# Beacon.net
KiCad netlist of a schematic drawn in Altium Designer
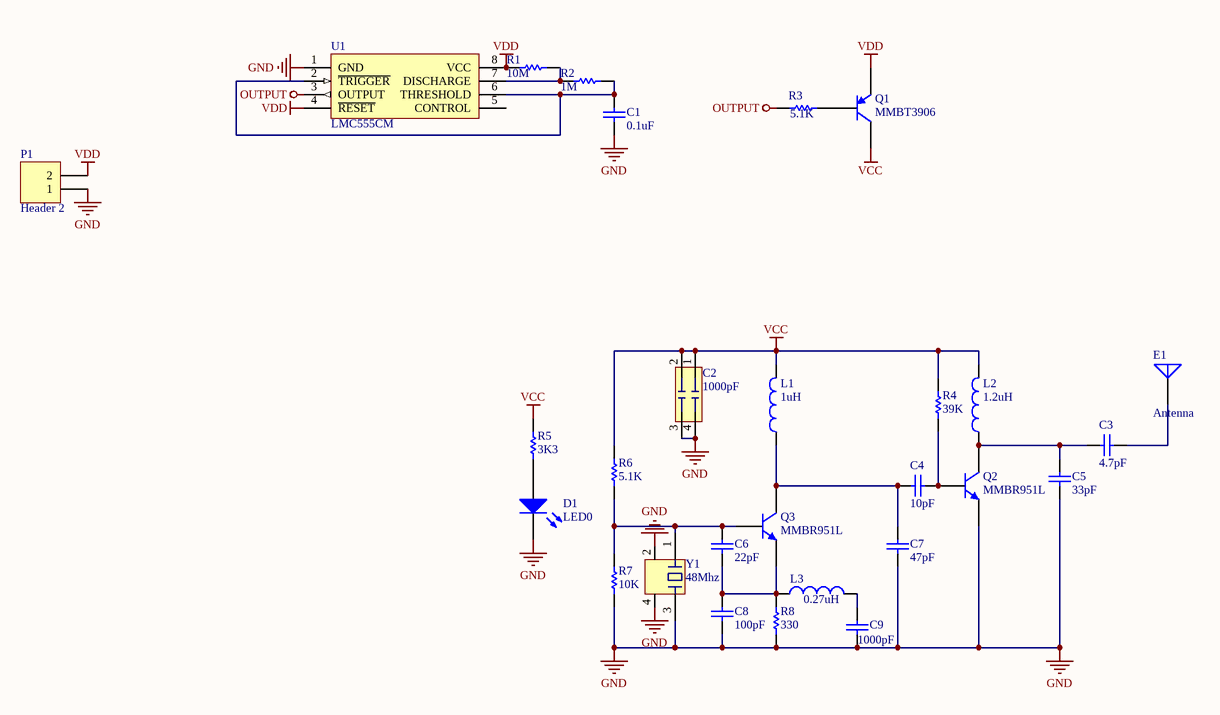
[diagram p0: Beacon.SchDoc]

(export (version "E")
  (design (tool "Eeschema 10.0.6"))
  (components
    (comp (ref "C1")
      (value "0.1uF")
      (footprint "0603")
      (description "Capacitor")
      (fields (field (name "PUBLISHER") "Altium Limited"))
      (libsource (lib "Miscellaneous Devices") (part "Cap"))
    )
    (comp (ref "C2") (value "1000pF") (footprint "CKCL22") (libsource (lib "Mert") (part "CAP ARRAY 2")))
    (comp (ref "C3")
      (value "4.7pF")
      (footprint "0402")
      (description "Capacitor")
      (fields (field (name "PUBLISHER") "Altium Limited"))
      (libsource (lib "Miscellaneous Devices") (part "Cap"))
    )
    (comp (ref "C4")
      (value "10pF")
      (footprint "0402")
      (description "Capacitor")
      (fields (field (name "PUBLISHER") "Altium Limited"))
      (libsource (lib "Miscellaneous Devices") (part "Cap"))
    )
    (comp (ref "C5")
      (value "33pF")
      (footprint "0402")
      (description "Capacitor")
      (fields (field (name "PUBLISHER") "Altium Limited"))
      (libsource (lib "Miscellaneous Devices") (part "Cap"))
    )
    (comp (ref "C6")
      (value "22pF")
      (footprint "0402")
      (description "Capacitor")
      (fields (field (name "PUBLISHER") "Altium Limited"))
      (libsource (lib "Miscellaneous Devices") (part "Cap"))
    )
    (comp (ref "C7")
      (value "47pF")
      (footprint "0402")
      (description "Capacitor")
      (fields (field (name "PUBLISHER") "Altium Limited"))
      (libsource (lib "Miscellaneous Devices") (part "Cap"))
    )
    (comp (ref "C8")
      (value "100pF")
      (footprint "0402")
      (description "Capacitor")
      (fields (field (name "PUBLISHER") "Altium Limited"))
      (libsource (lib "Miscellaneous Devices") (part "Cap"))
    )
    (comp (ref "C9")
      (value "1000pF")
      (footprint "0402")
      (description "Capacitor")
      (fields (field (name "PUBLISHER") "Altium Limited"))
      (libsource (lib "Miscellaneous Devices") (part "Cap"))
    )
    (comp (ref "D1")
      (value "LED0")
      (footprint "0402")
      (description "Typical INFRARED GaAs LED")
      (fields (field (name "PUBLISHER") "Altium Limited"))
      (libsource (lib "Miscellaneous Devices") (part "LED0"))
    )
    (comp (ref "E1")
      (value "Antenna")
      (footprint "PIN1")
      (description "Generic Antenna")
      (fields (field (name "PUBLISHER") "Altium Limited"))
      (libsource (lib "Miscellaneous Devices") (part "Antenna"))
    )
    (comp (ref "L1")
      (value "1uH")
      (footprint "1008")
      (description "Inductor")
      (fields (field (name "PUBLISHER") "Altium Limited"))
      (libsource (lib "Miscellaneous Devices") (part "Inductor"))
    )
    (comp (ref "L2")
      (value "1.2uH")
      (footprint "1008")
      (description "Inductor")
      (fields (field (name "PUBLISHER") "Altium Limited"))
      (libsource (lib "Miscellaneous Devices") (part "Inductor"))
    )
    (comp (ref "L3")
      (value "0.27uH")
      (footprint "0402")
      (description "Inductor")
      (fields (field (name "PUBLISHER") "Altium Limited"))
      (libsource (lib "Miscellaneous Devices") (part "Inductor"))
    )
    (comp (ref "P1")
      (value "Header 2")
      (footprint "HDR1X2")
      (description "Header, 2-Pin")
      (fields (field (name "PUBLISHER") "Altium Limited"))
      (libsource (lib "Miscellaneous Connectors") (part "Header 2"))
    )
    (comp (ref "Q1")
      (value "MMBT3906")
      (footprint "sot-923f")
      (description "PNP Switching Transistor")
      (fields (field (name "PUBLISHER") "Altium Limited"))
      (libsource (lib "Philips Discrete BJT - Low Power") (part "MMBT3906"))
    )
    (comp (ref "Q2")
      (value "MMBR951L")
      (footprint "sot-23")
      (description "NPN Bipolar Transistor")
      (fields (field (name "PUBLISHER") "Altium Limited"))
      (libsource (lib "Miscellaneous Devices") (part "NPN"))
    )
    (comp (ref "Q3")
      (value "MMBR951L")
      (footprint "sot-23")
      (description "NPN Bipolar Transistor")
      (fields (field (name "PUBLISHER") "Altium Limited"))
      (libsource (lib "Miscellaneous Devices") (part "NPN"))
    )
    (comp (ref "R1")
      (value "10M")
      (footprint "0402")
      (description "Resistor")
      (fields (field (name "PUBLISHER") "Altium Limited"))
      (libsource (lib "Miscellaneous Devices") (part "Res1"))
    )
    (comp (ref "R2")
      (value "1M")
      (footprint "0603")
      (description "Resistor")
      (fields (field (name "PUBLISHER") "Altium Limited"))
      (libsource (lib "Miscellaneous Devices") (part "Res1"))
    )
    (comp (ref "R3")
      (value "5.1K")
      (footprint "0402")
      (description "Resistor")
      (fields (field (name "PUBLISHER") "Altium Limited"))
      (libsource (lib "Miscellaneous Devices") (part "Res1"))
    )
    (comp (ref "R4")
      (value "39K")
      (footprint "0402")
      (description "Resistor")
      (fields (field (name "PUBLISHER") "Altium Limited"))
      (libsource (lib "Miscellaneous Devices") (part "Res1"))
    )
    (comp (ref "R5")
      (value "3K3")
      (footprint "0402")
      (description "Resistor")
      (fields (field (name "PUBLISHER") "Altium Limited"))
      (libsource (lib "Miscellaneous Devices") (part "Res1"))
    )
    (comp (ref "R6")
      (value "5.1K")
      (footprint "0402")
      (description "Resistor")
      (fields (field (name "PUBLISHER") "Altium Limited"))
      (libsource (lib "Miscellaneous Devices") (part "Res1"))
    )
    (comp (ref "R7")
      (value "10K")
      (footprint "0402")
      (description "Resistor")
      (fields (field (name "PUBLISHER") "Altium Limited"))
      (libsource (lib "Miscellaneous Devices") (part "Res1"))
    )
    (comp (ref "R8")
      (value "330")
      (footprint "0402")
      (description "Resistor")
      (fields (field (name "PUBLISHER") "Altium Limited"))
      (libsource (lib "Miscellaneous Devices") (part "Res1"))
    )
    (comp (ref "U1") (value "LMC555CM") (footprint "vssop8") (libsource (lib "Mert") (part "LMC555CM")))
    (comp (ref "Y1") (value "48Mhz") (footprint "Xtal 3.2x2.5") (libsource (lib "Mert") (part "Xtal 4pin")))
  )
  (nets
    (net (code "1") (name "GND") (class "Default")
      (node (ref "C1") (pin "1") (pinfunction "1_1") (pintype "passive"))
      (node (ref "C2") (pin "3") (pinfunction "3_3") (pintype "passive"))
      (node (ref "C2") (pin "4") (pinfunction "4_4") (pintype "passive"))
      (node (ref "C5") (pin "1") (pinfunction "1_1") (pintype "passive"))
      (node (ref "C7") (pin "1") (pinfunction "1_1") (pintype "passive"))
      (node (ref "C8") (pin "1") (pinfunction "1_1") (pintype "passive"))
      (node (ref "C9") (pin "2") (pinfunction "2_2") (pintype "passive"))
      (node (ref "D1") (pin "2") (pinfunction "K_2") (pintype "passive"))
      (node (ref "P1") (pin "1") (pinfunction "1_1") (pintype "passive"))
      (node (ref "Q2") (pin "3") (pinfunction "E_3") (pintype "passive"))
      (node (ref "R7") (pin "1") (pinfunction "1_1") (pintype "passive"))
      (node (ref "R8") (pin "1") (pinfunction "1_1") (pintype "passive"))
      (node (ref "U1") (pin "1") (pinfunction "GND_1") (pintype "power_in"))
      (node (ref "Y1") (pin "2") (pinfunction "2_2") (pintype "passive"))
      (node (ref "Y1") (pin "3") (pinfunction "3_3") (pintype "passive"))
      (node (ref "Y1") (pin "4") (pinfunction "4_4") (pintype "passive"))
    )
    (net (code "2") (name "Net-(C9-Pad1)") (class "Default")
      (node (ref "C9") (pin "1") (pinfunction "1_1") (pintype "passive"))
      (node (ref "L3") (pin "2") (pinfunction "2_2") (pintype "passive"))
    )
    (net (code "3") (name "Net-(D1-A)") (class "Default")
      (node (ref "D1") (pin "1") (pinfunction "A_1") (pintype "passive"))
      (node (ref "R5") (pin "1") (pinfunction "1_1") (pintype "passive"))
    )
    (net (code "4") (name "Net-(E1-A)") (class "Default")
      (node (ref "C3") (pin "1") (pinfunction "1_1") (pintype "passive"))
      (node (ref "E1") (pin "1") (pinfunction "A_1") (pintype "passive"))
    )
    (net (code "5") (name "Net-(Q1-B)") (class "Default")
      (node (ref "Q1") (pin "1") (pinfunction "B_1") (pintype "passive"))
      (node (ref "R3") (pin "2") (pinfunction "2_2") (pintype "passive"))
    )
    (net (code "6") (name "Net-(Q2-B)") (class "Default")
      (node (ref "C4") (pin "1") (pinfunction "1_1") (pintype "passive"))
      (node (ref "Q2") (pin "2") (pinfunction "B_2") (pintype "passive"))
      (node (ref "R4") (pin "1") (pinfunction "1_1") (pintype "passive"))
    )
    (net (code "7") (name "Net-(Q2-C)") (class "Default")
      (node (ref "C3") (pin "2") (pinfunction "2_2") (pintype "passive"))
      (node (ref "C5") (pin "2") (pinfunction "2_2") (pintype "passive"))
      (node (ref "L2") (pin "1") (pinfunction "1_1") (pintype "passive"))
      (node (ref "Q2") (pin "1") (pinfunction "C_1") (pintype "passive"))
    )
    (net (code "8") (name "Net-(Q3-B)") (class "Default")
      (node (ref "C6") (pin "2") (pinfunction "2_2") (pintype "passive"))
      (node (ref "Q3") (pin "2") (pinfunction "B_2") (pintype "passive"))
      (node (ref "R6") (pin "1") (pinfunction "1_1") (pintype "passive"))
      (node (ref "R7") (pin "2") (pinfunction "2_2") (pintype "passive"))
      (node (ref "Y1") (pin "1") (pinfunction "1_1") (pintype "passive"))
    )
    (net (code "9") (name "Net-(Q3-C)") (class "Default")
      (node (ref "C4") (pin "2") (pinfunction "2_2") (pintype "passive"))
      (node (ref "C7") (pin "2") (pinfunction "2_2") (pintype "passive"))
      (node (ref "L1") (pin "1") (pinfunction "1_1") (pintype "passive"))
      (node (ref "Q3") (pin "1") (pinfunction "C_1") (pintype "passive"))
    )
    (net (code "10") (name "Net-(Q3-E)") (class "Default")
      (node (ref "C6") (pin "1") (pinfunction "1_1") (pintype "passive"))
      (node (ref "C8") (pin "2") (pinfunction "2_2") (pintype "passive"))
      (node (ref "L3") (pin "1") (pinfunction "1_1") (pintype "passive"))
      (node (ref "Q3") (pin "3") (pinfunction "E_3") (pintype "passive"))
      (node (ref "R8") (pin "2") (pinfunction "2_2") (pintype "passive"))
    )
    (net (code "11") (name "Net-(U1-DISCHARGE)") (class "Default")
      (node (ref "R1") (pin "1") (pinfunction "1_1") (pintype "passive"))
      (node (ref "R2") (pin "2") (pinfunction "2_2") (pintype "passive"))
      (node (ref "U1") (pin "7") (pinfunction "DISCHARGE_7") (pintype "passive"))
    )
    (net (code "12") (name "Net-(U1-THRESHOLD)") (class "Default")
      (node (ref "C1") (pin "2") (pinfunction "2_2") (pintype "passive"))
      (node (ref "R2") (pin "1") (pinfunction "1_1") (pintype "passive"))
      (node (ref "U1") (pin "2") (pinfunction "~{TRIGGER}_2") (pintype "input"))
      (node (ref "U1") (pin "6") (pinfunction "THRESHOLD_6") (pintype "passive"))
    )
    (net (code "13") (name "OUTPUT") (class "Default")
      (node (ref "R3") (pin "1") (pinfunction "1_1") (pintype "passive"))
      (node (ref "U1") (pin "3") (pinfunction "OUTPUT_3") (pintype "output"))
    )
    (net (code "14") (name "VCC") (class "Default")
      (node (ref "C2") (pin "1") (pinfunction "1_1") (pintype "passive"))
      (node (ref "C2") (pin "2") (pinfunction "2_2") (pintype "passive"))
      (node (ref "L1") (pin "2") (pinfunction "2_2") (pintype "passive"))
      (node (ref "L2") (pin "2") (pinfunction "2_2") (pintype "passive"))
      (node (ref "Q1") (pin "3") (pinfunction "C_3") (pintype "passive"))
      (node (ref "R4") (pin "2") (pinfunction "2_2") (pintype "passive"))
      (node (ref "R5") (pin "2") (pinfunction "2_2") (pintype "passive"))
      (node (ref "R6") (pin "2") (pinfunction "2_2") (pintype "passive"))
    )
    (net (code "15") (name "VDD") (class "Default")
      (node (ref "P1") (pin "2") (pinfunction "2_2") (pintype "passive"))
      (node (ref "Q1") (pin "2") (pinfunction "E_2") (pintype "passive"))
      (node (ref "R1") (pin "2") (pinfunction "2_2") (pintype "passive"))
      (node (ref "U1") (pin "4") (pinfunction "~{RESET}_4") (pintype "passive"))
      (node (ref "U1") (pin "8") (pinfunction "VCC_8") (pintype "power_in"))
    )
    (net (code "16") (name "unconnected-(U1-CONTROL-Pad5)") (class "Default")
      (node (ref "U1") (pin "5") (pinfunction "CONTROL_5") (pintype "passive"))
    )
  )
)
